# untitled.net
KiCad netlist of a schematic drawn in EAGLE
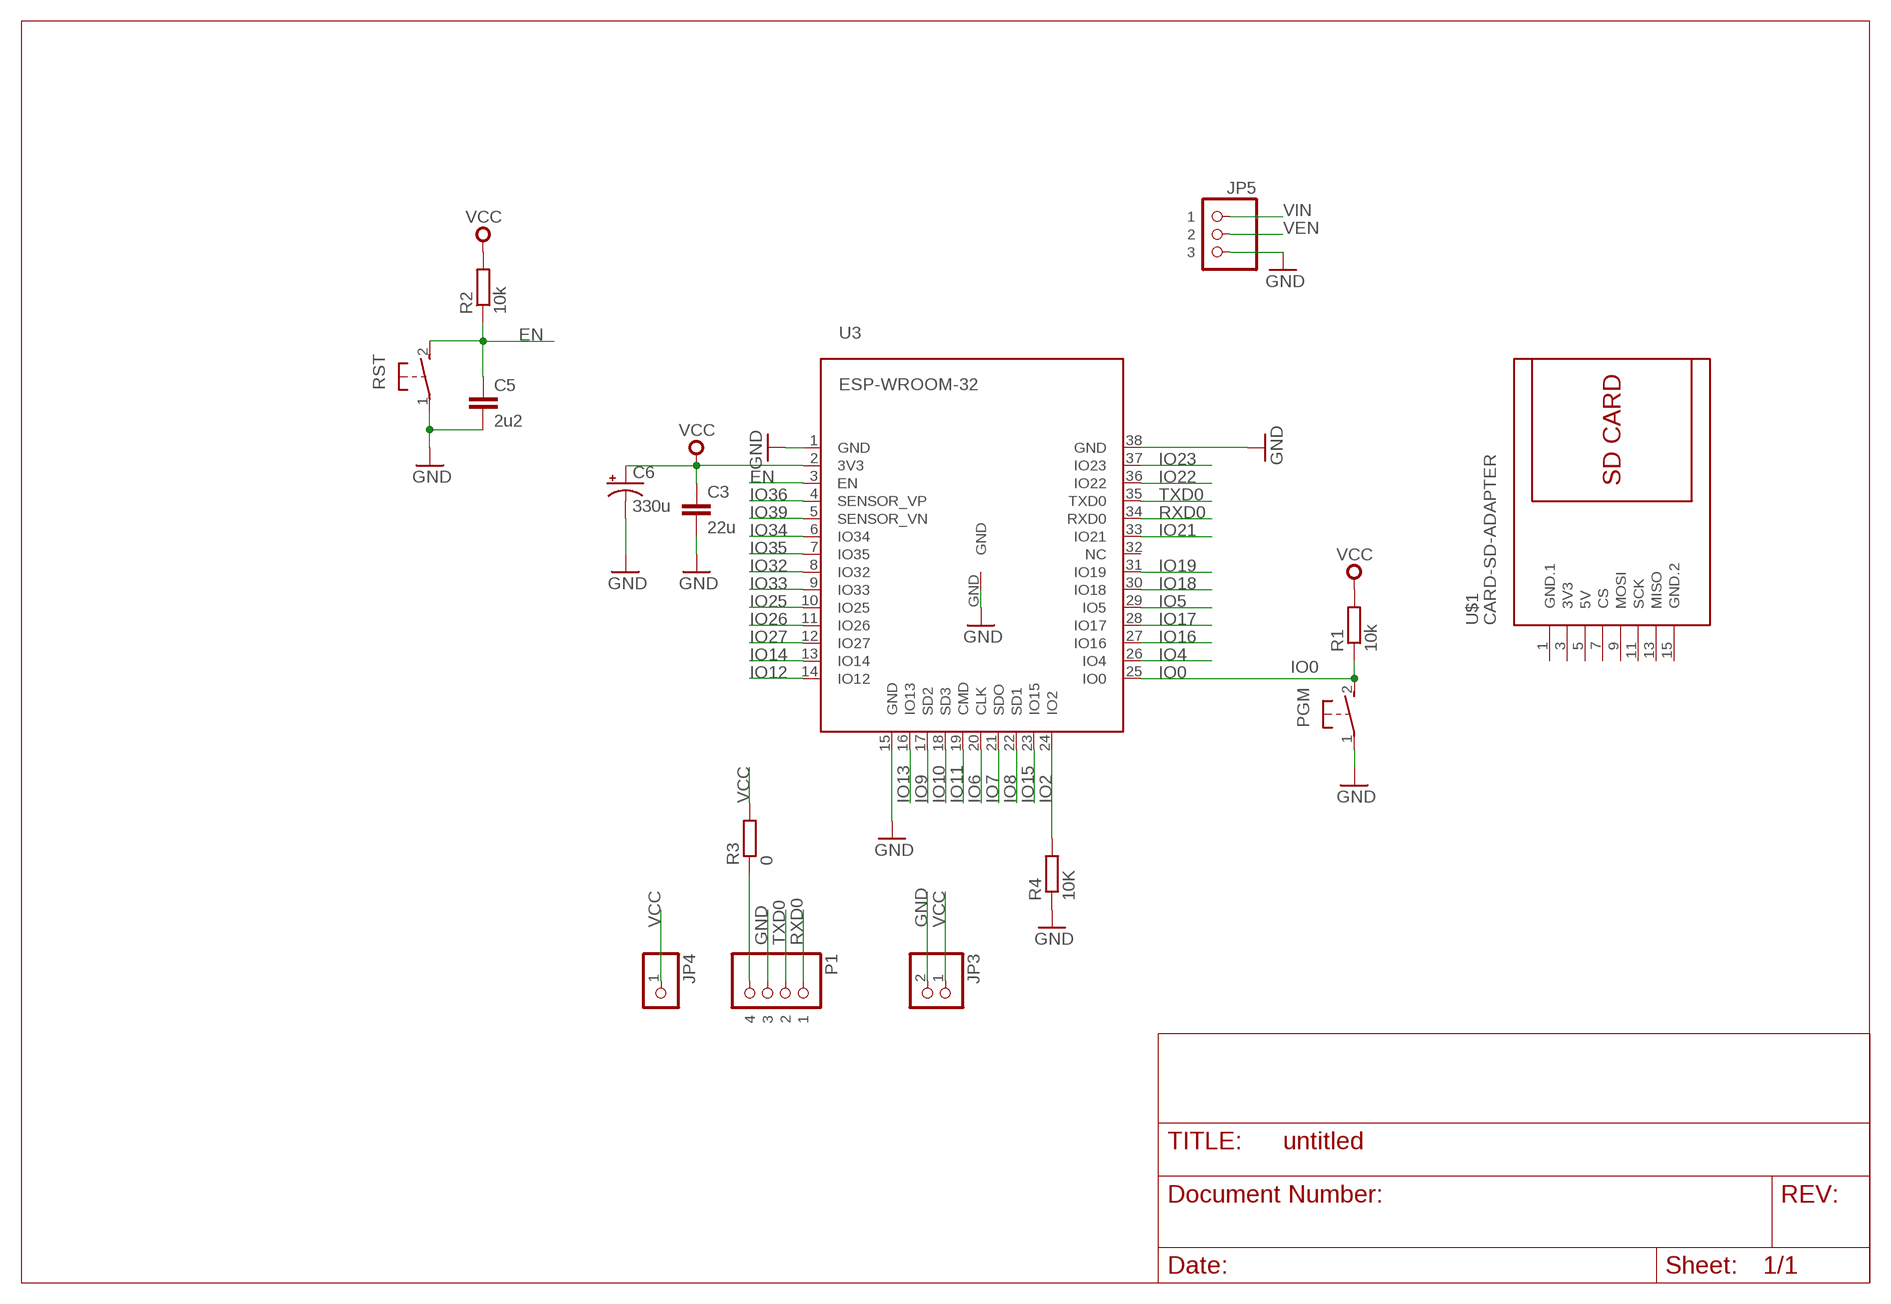
[diagram p0: schematic, sheet 1]

(export (version "E")
  (design (tool "Eeschema 10.0.6"))
  (components
    (comp (ref "C3")
      (value "22u")
      (footprint "eagle-import:0805")
      (libsource (lib "eagle-import") (part "CAP0805"))
    )
    (comp (ref "C5")
      (value "2u2")
      (footprint "eagle-import:C0603")
      (libsource (lib "eagle-import") (part "C-EUC0603"))
    )
    (comp (ref "C6")
      (value "330u")
      (footprint "eagle-import:VISHAY_C")
      (libsource (lib "eagle-import") (part "CAP_POLSMD"))
    )
    (comp (ref "JP3")
      (value "HEADER-1X2ROUND")
      (footprint "eagle-import:1X02_ROUND")
      (libsource (lib "eagle-import") (part "HEADER-1X2ROUND"))
    )
    (comp (ref "JP4")
      (value "HEADER-1X1ROUND")
      (footprint "eagle-import:1X01_ROUND")
      (libsource (lib "eagle-import") (part "HEADER-1X1ROUND"))
    )
    (comp (ref "JP5")
      (value "HEADER-1X3ROUND")
      (footprint "eagle-import:1X03_ROUND")
      (libsource (lib "eagle-import") (part "HEADER-1X3ROUND"))
    )
    (comp (ref "P1")
      (value "HEADER-1X4ROUND")
      (footprint "eagle-import:1X04_ROUND")
      (libsource (lib "eagle-import") (part "HEADER-1X4ROUND"))
    )
    (comp (ref "PGM")
      (value "DTSM-3")
      (footprint "eagle-import:DTSM-3")
      (libsource (lib "eagle-import") (part "DTSM-3"))
    )
    (comp (ref "R1")
      (value "10k")
      (footprint "eagle-import:R0603")
      (libsource (lib "eagle-import") (part "R-EU_R0603"))
    )
    (comp (ref "R2")
      (value "10k")
      (footprint "eagle-import:R0603")
      (libsource (lib "eagle-import") (part "R-EU_R0603"))
    )
    (comp (ref "R3")
      (value "0")
      (footprint "eagle-import:R0603")
      (libsource (lib "eagle-import") (part "R-EU_R0603"))
    )
    (comp (ref "R4")
      (value "10K")
      (footprint "eagle-import:R0603")
      (libsource (lib "eagle-import") (part "R-EU_R0603"))
    )
    (comp (ref "RST")
      (value "DTSM-3")
      (footprint "eagle-import:DTSM-3")
      (libsource (lib "eagle-import") (part "DTSM-3"))
    )
    (comp (ref "U$1")
      (value "CARD-SD-ADAPTER")
      (footprint "eagle-import:CARD-SD-ADAPTER")
      (libsource (lib "eagle-import") (part "CARD-SD-ADAPTER"))
    )
    (comp (ref "U3")
      (value "ESP-WROOM-32")
      (footprint "eagle-import:ESP-WROOM-32")
      (libsource (lib "eagle-import") (part "ESP-WROOM-32"))
    )
  )
  (nets
    (net (code "1") (name "/3V3") (class "Default")
      (node (ref "U$1") (pin "3") (pinfunction "3V3_3") (pintype "power_in"))
    )
    (net (code "2") (name "/5V") (class "Default")
      (node (ref "U$1") (pin "5") (pinfunction "5V_5") (pintype "power_in"))
    )
    (net (code "3") (name "/EN") (class "Default")
      (node (ref "C5") (pin "1") (pinfunction "1_1") (pintype "passive"))
      (node (ref "R2") (pin "1") (pinfunction "1_1") (pintype "passive"))
      (node (ref "RST") (pin "2") (pinfunction "2_2") (pintype "passive"))
      (node (ref "U3") (pin "3") (pinfunction "EN_3") (pintype "bidirectional"))
    )
    (net (code "4") (name "/GND.1") (class "Default")
      (node (ref "U$1") (pin "1") (pinfunction "GND.1_1") (pintype "power_in"))
    )
    (net (code "5") (name "/GND.2") (class "Default")
      (node (ref "U$1") (pin "15") (pinfunction "GND.2_15") (pintype "power_in"))
    )
    (net (code "6") (name "/IO0") (class "Default")
      (node (ref "PGM") (pin "2") (pinfunction "2_2") (pintype "passive"))
      (node (ref "R1") (pin "1") (pinfunction "1_1") (pintype "passive"))
      (node (ref "U3") (pin "25") (pinfunction "IO0_25") (pintype "bidirectional"))
    )
    (net (code "7") (name "/IO2") (class "Default")
      (node (ref "R4") (pin "2") (pinfunction "2_2") (pintype "passive"))
      (node (ref "U3") (pin "24") (pinfunction "IO2_24") (pintype "bidirectional"))
    )
    (net (code "8") (name "/IO4") (class "Default")
      (node (ref "U3") (pin "26") (pinfunction "IO4_26") (pintype "bidirectional"))
    )
    (net (code "9") (name "/IO5") (class "Default")
      (node (ref "U3") (pin "29") (pinfunction "IO5_29") (pintype "bidirectional"))
    )
    (net (code "10") (name "/IO6") (class "Default")
      (node (ref "U3") (pin "20") (pinfunction "CLK_20") (pintype "bidirectional"))
    )
    (net (code "11") (name "/IO7") (class "Default")
      (node (ref "U3") (pin "21") (pinfunction "SDO_21") (pintype "bidirectional"))
    )
    (net (code "12") (name "/IO8") (class "Default")
      (node (ref "U3") (pin "22") (pinfunction "SD1_22") (pintype "bidirectional"))
    )
    (net (code "13") (name "/IO9") (class "Default")
      (node (ref "U3") (pin "17") (pinfunction "SD2_17") (pintype "bidirectional"))
    )
    (net (code "14") (name "/IO10") (class "Default")
      (node (ref "U3") (pin "18") (pinfunction "SD3_18") (pintype "bidirectional"))
    )
    (net (code "15") (name "/IO11") (class "Default")
      (node (ref "U3") (pin "19") (pinfunction "CMD_19") (pintype "bidirectional"))
    )
    (net (code "16") (name "/IO12") (class "Default")
      (node (ref "U3") (pin "14") (pinfunction "IO12_14") (pintype "bidirectional"))
    )
    (net (code "17") (name "/IO13") (class "Default")
      (node (ref "U3") (pin "16") (pinfunction "IO13_16") (pintype "bidirectional"))
    )
    (net (code "18") (name "/IO14") (class "Default")
      (node (ref "U3") (pin "13") (pinfunction "IO14_13") (pintype "bidirectional"))
    )
    (net (code "19") (name "/IO15") (class "Default")
      (node (ref "U3") (pin "23") (pinfunction "IO15_23") (pintype "bidirectional"))
    )
    (net (code "20") (name "/IO16") (class "Default")
      (node (ref "U3") (pin "27") (pinfunction "IO16_27") (pintype "bidirectional"))
    )
    (net (code "21") (name "/IO17") (class "Default")
      (node (ref "U3") (pin "28") (pinfunction "IO17_28") (pintype "bidirectional"))
    )
    (net (code "22") (name "/IO18") (class "Default")
      (node (ref "U3") (pin "30") (pinfunction "IO18_30") (pintype "bidirectional"))
    )
    (net (code "23") (name "/IO19") (class "Default")
      (node (ref "U3") (pin "31") (pinfunction "IO19_31") (pintype "bidirectional"))
    )
    (net (code "24") (name "/IO21") (class "Default")
      (node (ref "U3") (pin "33") (pinfunction "IO21_33") (pintype "bidirectional"))
    )
    (net (code "25") (name "/IO22") (class "Default")
      (node (ref "U3") (pin "36") (pinfunction "IO22_36") (pintype "bidirectional"))
    )
    (net (code "26") (name "/IO23") (class "Default")
      (node (ref "U3") (pin "37") (pinfunction "IO23_37") (pintype "bidirectional"))
    )
    (net (code "27") (name "/IO25") (class "Default")
      (node (ref "U3") (pin "10") (pinfunction "IO25_10") (pintype "bidirectional"))
    )
    (net (code "28") (name "/IO26") (class "Default")
      (node (ref "U3") (pin "11") (pinfunction "IO26_11") (pintype "bidirectional"))
    )
    (net (code "29") (name "/IO27") (class "Default")
      (node (ref "U3") (pin "12") (pinfunction "IO27_12") (pintype "bidirectional"))
    )
    (net (code "30") (name "/IO32") (class "Default")
      (node (ref "U3") (pin "8") (pinfunction "IO32_8") (pintype "bidirectional"))
    )
    (net (code "31") (name "/IO33") (class "Default")
      (node (ref "U3") (pin "9") (pinfunction "IO33_9") (pintype "bidirectional"))
    )
    (net (code "32") (name "/IO34") (class "Default")
      (node (ref "U3") (pin "6") (pinfunction "IO34_6") (pintype "bidirectional"))
    )
    (net (code "33") (name "/IO35") (class "Default")
      (node (ref "U3") (pin "7") (pinfunction "IO35_7") (pintype "bidirectional"))
    )
    (net (code "34") (name "/IO36") (class "Default")
      (node (ref "U3") (pin "4") (pinfunction "SENSOR_VP_4") (pintype "bidirectional"))
    )
    (net (code "35") (name "/IO39") (class "Default")
      (node (ref "U3") (pin "5") (pinfunction "SENSOR_VN_5") (pintype "bidirectional"))
    )
    (net (code "36") (name "/RXD0") (class "Default")
      (node (ref "P1") (pin "1") (pinfunction "1_1") (pintype "passive"))
      (node (ref "U3") (pin "34") (pinfunction "RXD0_34") (pintype "bidirectional"))
    )
    (net (code "37") (name "/TXD0") (class "Default")
      (node (ref "P1") (pin "2") (pinfunction "2_2") (pintype "passive"))
      (node (ref "U3") (pin "35") (pinfunction "TXD0_35") (pintype "bidirectional"))
    )
    (net (code "38") (name "/VEN") (class "Default")
      (node (ref "JP5") (pin "2") (pinfunction "2_2") (pintype "passive"))
    )
    (net (code "39") (name "/VIN") (class "Default")
      (node (ref "JP5") (pin "1") (pinfunction "1_1") (pintype "passive"))
    )
    (net (code "40") (name "GND") (class "Default")
      (node (ref "C3") (pin "2") (pinfunction "2_2") (pintype "passive"))
      (node (ref "C5") (pin "2") (pinfunction "2_2") (pintype "passive"))
      (node (ref "C6") (pin "-") (pinfunction "-_-") (pintype "passive"))
      (node (ref "JP3") (pin "2") (pinfunction "2_2") (pintype "passive"))
      (node (ref "JP5") (pin "3") (pinfunction "3_3") (pintype "passive"))
      (node (ref "P1") (pin "3") (pinfunction "3_3") (pintype "passive"))
      (node (ref "PGM") (pin "1") (pinfunction "1_1") (pintype "passive"))
      (node (ref "R4") (pin "1") (pinfunction "1_1") (pintype "passive"))
      (node (ref "RST") (pin "1") (pinfunction "1_1") (pintype "passive"))
      (node (ref "U3") (pin "1") (pinfunction "GND_1") (pintype "bidirectional"))
      (node (ref "U3") (pin "15") (pinfunction "GND_15") (pintype "bidirectional"))
      (node (ref "U3") (pin "38") (pinfunction "GND_38") (pintype "bidirectional"))
      (node (ref "U3") (pin "GND") (pinfunction "GND_GND") (pintype "bidirectional"))
    )
    (net (code "41") (name "Net-(P1-Pad4)") (class "Default")
      (node (ref "P1") (pin "4") (pinfunction "4_4") (pintype "passive"))
      (node (ref "R3") (pin "1") (pinfunction "1_1") (pintype "passive"))
    )
    (net (code "42") (name "VCC") (class "Default")
      (node (ref "C3") (pin "1") (pinfunction "1_1") (pintype "passive"))
      (node (ref "C6") (pin "+") (pinfunction "+_+") (pintype "passive"))
      (node (ref "JP3") (pin "1") (pinfunction "1_1") (pintype "passive"))
      (node (ref "JP4") (pin "1") (pinfunction "1_1") (pintype "passive"))
      (node (ref "R1") (pin "2") (pinfunction "2_2") (pintype "passive"))
      (node (ref "R2") (pin "2") (pinfunction "2_2") (pintype "passive"))
      (node (ref "R3") (pin "2") (pinfunction "2_2") (pintype "passive"))
      (node (ref "U3") (pin "2") (pinfunction "3V3_2") (pintype "bidirectional"))
    )
    (net (code "43") (name "unconnected-(U$1-CS-Pad7)") (class "Default")
      (node (ref "U$1") (pin "7") (pinfunction "CS_7") (pintype "bidirectional"))
    )
    (net (code "44") (name "unconnected-(U$1-MISO-Pad13)") (class "Default")
      (node (ref "U$1") (pin "13") (pinfunction "MISO_13") (pintype "bidirectional"))
    )
    (net (code "45") (name "unconnected-(U$1-MOSI-Pad9)") (class "Default")
      (node (ref "U$1") (pin "9") (pinfunction "MOSI_9") (pintype "bidirectional"))
    )
    (net (code "46") (name "unconnected-(U$1-SCK-Pad11)") (class "Default")
      (node (ref "U$1") (pin "11") (pinfunction "SCK_11") (pintype "bidirectional"))
    )
    (net (code "47") (name "unconnected-(U3-NC-Pad32)") (class "Default")
      (node (ref "U3") (pin "32") (pinfunction "NC_32") (pintype "bidirectional"))
    )
  )
)
